# medusa-charger.net
KiCad netlist of a schematic drawn in Altium Designer
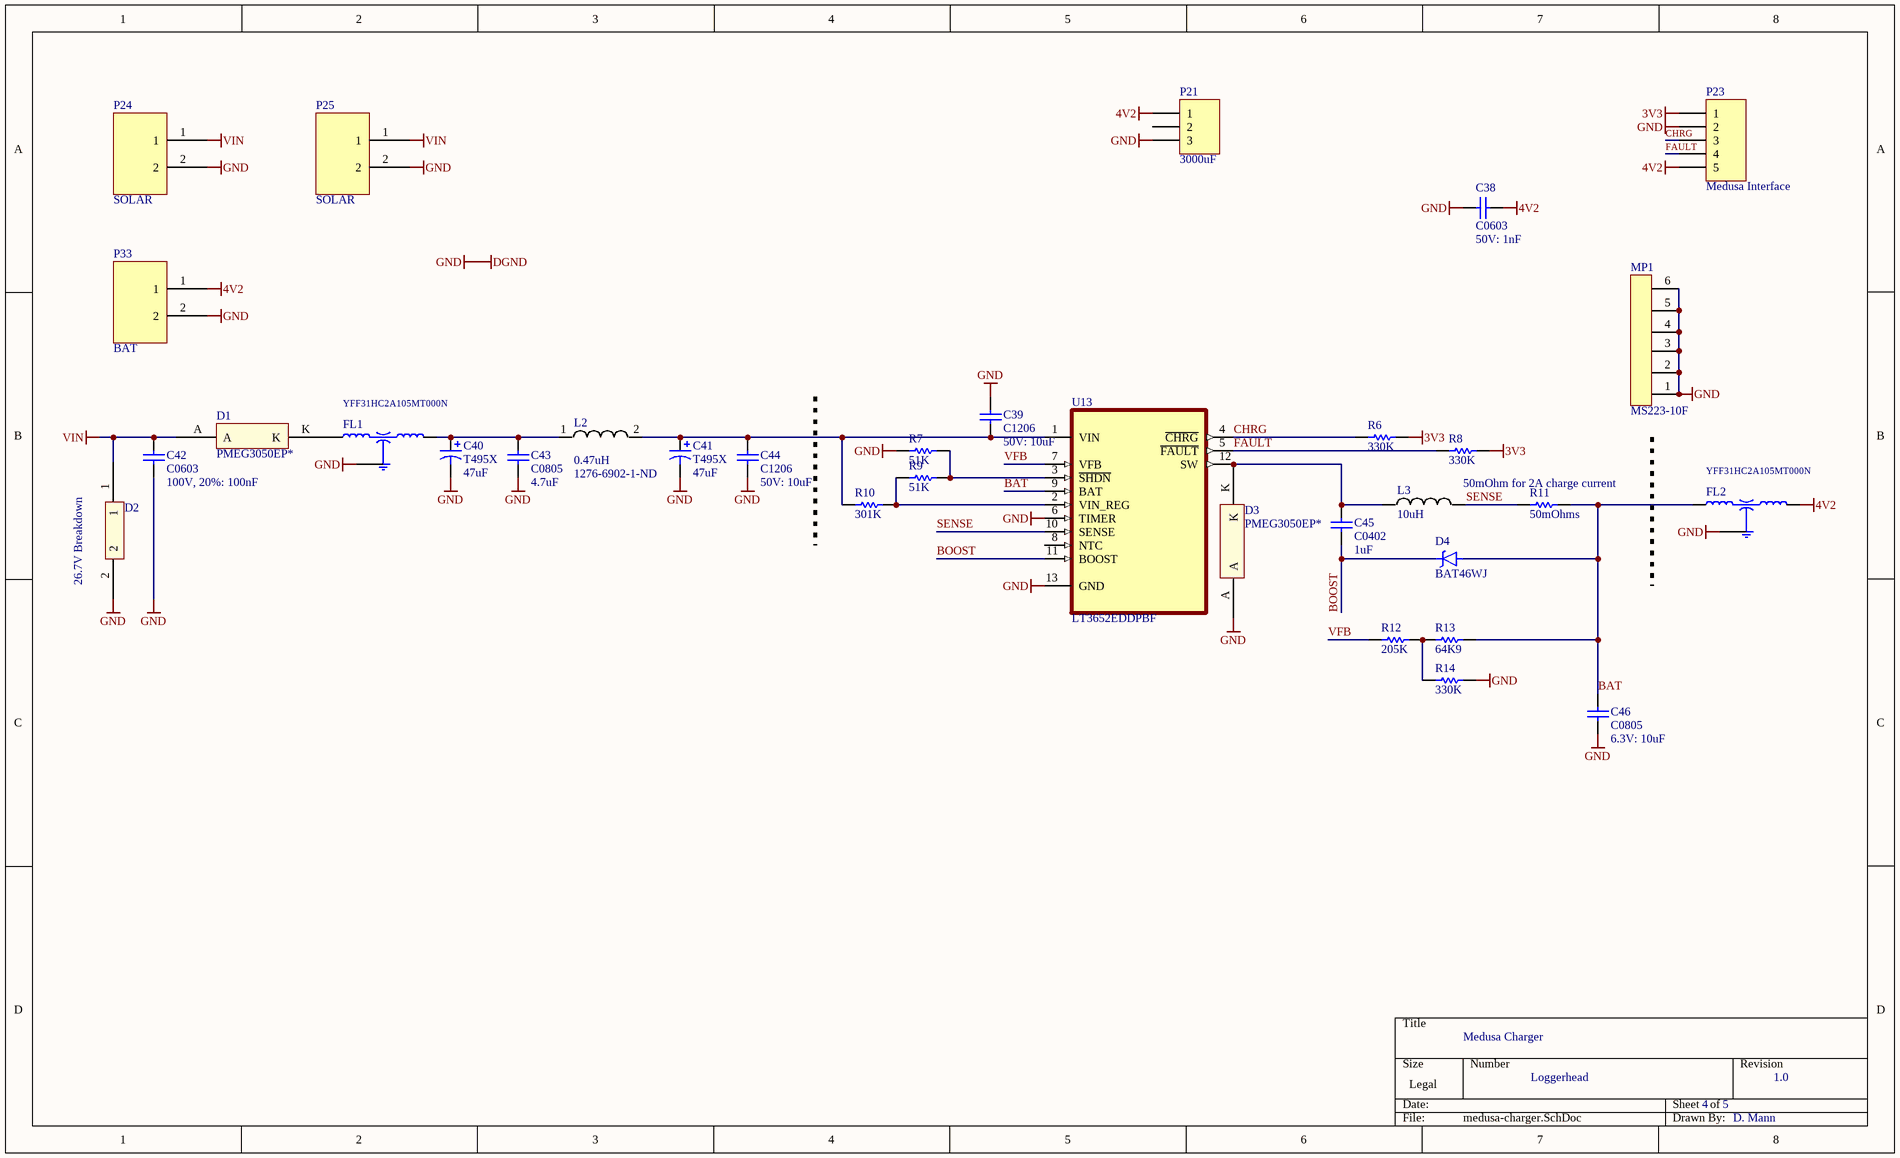
[diagram p0: medusa-charger.SchDoc]

(export (version "E")
  (design (tool "Eeschema 10.0.6"))
  (components
    (comp (ref "C38")
      (value "C0603")
      (footprint "0603")
      (description "Ceramic Chip Capacitor - Standard")
      (fields (field (name "50V") "1nF") (field (name "PUBLISHER") "Altium Limited"))
      (libsource (lib "KEMET Chip Capacitor") (part "C0603"))
    )
    (comp (ref "C39")
      (value "C1206")
      (footprint "1206")
      (description "Ceramic Chip Capacitor - Standard")
      (fields (field (name "50V") "10uF") (field (name "PUBLISHER") "Altium Limited"))
      (libsource (lib "KEMET Chip Capacitor") (part "C1206"))
    )
    (comp (ref "C40")
      (value "T495X")
      (footprint "X")
      (description "Solid Tantalum Chip Capacitor, Standard T495 Series - 35V 10%")
      (fields (field (name "ALTIUM_VALUE") "47uF") (field (name "PUBLISHER") "Altium Limited"))
      (libsource (lib "KEMET Chip Capacitor") (part "T495X"))
    )
    (comp (ref "C41")
      (value "T495X")
      (footprint "X")
      (description "Solid Tantalum Chip Capacitor, Standard T495 Series - 35V 10%")
      (fields (field (name "ALTIUM_VALUE") "47uF") (field (name "PUBLISHER") "Altium Limited"))
      (libsource (lib "KEMET Chip Capacitor") (part "T495X"))
    )
    (comp (ref "C42")
      (value "C0603")
      (footprint "0603")
      (description "100V 20%")
      (fields (field (name "100V, 20%") "100nF") (field (name "PUBLISHER") "Altium Limited"))
      (libsource (lib "KEMET Chip Capacitor") (part "C0603"))
    )
    (comp (ref "C43")
      (value "C0805")
      (footprint "0805")
      (description "Ceramic Chip Capacitor - Standard")
      (fields (field (name "ALTIUM_VALUE") "4.7uF") (field (name "PUBLISHER") "Altium Limited"))
      (libsource (lib "KEMET Chip Capacitor") (part "C0805"))
    )
    (comp (ref "C44")
      (value "C1206")
      (footprint "1206")
      (description "Ceramic Chip Capacitor - Standard")
      (fields (field (name "50V") "10uF") (field (name "PUBLISHER") "Altium Limited"))
      (libsource (lib "KEMET Chip Capacitor") (part "C1206"))
    )
    (comp (ref "C45")
      (value "C0402")
      (footprint "0402")
      (description "Ceramic Chip Capacitor - Standard")
      (fields (field (name "ALTIUM_VALUE") "1uF") (field (name "PUBLISHER") "Altium Limited"))
      (libsource (lib "KEMET Chip Capacitor") (part "C0402"))
    )
    (comp (ref "C46")
      (value "C0805")
      (footprint "0805")
      (description "Ceramic Chip Capacitor - Standard")
      (fields (field (name "6.3V") "10uF") (field (name "PUBLISHER") "Altium Limited"))
      (libsource (lib "KEMET Chip Capacitor") (part "C0805"))
    )
    (comp (ref "D1")
      (value "PMEG3050EP*")
      (footprint "Diode_PMEG3050EP")
      (libsource (lib "") (part "Diode_PMEG3050EP_1"))
    )
    (comp (ref "D2")
      (value "26.7V Breakdown")
      (footprint "SMBJ24CA")
      (libsource (lib "Loggerhead") (part "SMBJ24CA"))
    )
    (comp (ref "D3")
      (value "PMEG3050EP*")
      (footprint "Diode_PMEG3050EP")
      (libsource (lib "Loggerhead") (part "Diode_PMEG3050EP"))
    )
    (comp (ref "D4")
      (value "BAT46WJ")
      (footprint "SOD-323")
      (description "Diode Schottky 100V 250mA (DC) Surface Mount SOD-323F")
      (fields (field (name "MF") "NXP Semiconductors"))
      (libsource (lib "BAT46WJ") (part "BAT46WJ"))
    )
    (comp (ref "FL1")
      (value "YFF31HC2A105MT000N")
      (footprint "FIL_YFF31HC2A105MT000N")
      (description "1ÂµF Feed Through Capacitor 100V 6A 5mOhm 1206 (3216 Metric), 4 PC Pad")
      (fields (field (name "MF") "TDK"))
      (libsource (lib "YFF31HC2A105MT000N") (part "YFF31HC2A105MT000N"))
    )
    (comp (ref "FL2")
      (value "YFF31HC2A105MT000N")
      (footprint "FIL_YFF31HC2A105MT000N")
      (description "1ÂµF Feed Through Capacitor 100V 6A 5mOhm 1206 (3216 Metric), 4 PC Pad")
      (fields (field (name "MF") "TDK"))
      (libsource (lib "YFF31HC2A105MT000N") (part "YFF31HC2A105MT000N"))
    )
    (comp (ref "L2")
      (value "0.47uH")
      (footprint "Inductor2016")
      (fields
        (field (name "SUPPLIER PART NUMBER 1") "1276-6902-1-ND")
        (field (name "Comment") "Inductor2016")
      )
      (libsource (lib "Loggerhead") (part "Inductor2016"))
    )
    (comp (ref "L3")
      (value "10uH")
      (footprint "Inductor0630CDMCD")
      (libsource (lib "Loggerhead") (part "Inductor_0630CDMCD"))
    )
    (comp (ref "MP1")
      (value "MS223-10F")
      (footprint "MS223-10F")
      (description "RF Shield")
      (libsource (lib "Loggerhead") (part "MS223-10F"))
    )
    (comp (ref "P21")
      (value "3000uF")
      (footprint "HDR1X3")
      (description "Header, 3-Pin")
      (fields (field (name "PUBLISHER") "Altium Limited"))
      (libsource (lib "Miscellaneous Connectors") (part "Header 3"))
    )
    (comp (ref "P23")
      (value "Medusa Interface")
      (footprint "HDR1X5")
      (description "Header, 5-Pin")
      (fields (field (name "PUBLISHER") "Altium Limited"))
      (libsource (lib "Miscellaneous Connectors") (part "Header 5"))
    )
    (comp (ref "P24")
      (value "SOLAR")
      (footprint "HDR_2x1_2mm")
      (libsource (lib "Loggerhead") (part "HDR_2x1_2mm"))
    )
    (comp (ref "P25")
      (value "SOLAR")
      (footprint "HDR_2x1_2mm")
      (libsource (lib "Loggerhead") (part "HDR_2x1_2mm"))
    )
    (comp (ref "P33")
      (value "BAT")
      (footprint "HDR_2x1_2mm")
      (libsource (lib "Loggerhead") (part "HDR_2x1_2mm"))
    )
    (comp (ref "R6")
      (value "330K")
      (footprint "3-0603")
      (fields (field (name "PUBLISHER") "Altium Limited"))
      (libsource (lib "Panasonic Resistor") (part "ERJ3EK"))
    )
    (comp (ref "R7")
      (value "51K")
      (footprint "3-0603")
      (fields (field (name "PUBLISHER") "Altium Limited"))
      (libsource (lib "Panasonic Resistor") (part "ERJ3EK"))
    )
    (comp (ref "R8")
      (value "330K")
      (footprint "3-0603")
      (fields (field (name "PUBLISHER") "Altium Limited"))
      (libsource (lib "Panasonic Resistor") (part "ERJ3EK"))
    )
    (comp (ref "R9")
      (value "51K")
      (footprint "3-0603")
      (fields (field (name "PUBLISHER") "Altium Limited"))
      (libsource (lib "Panasonic Resistor") (part "ERJ3EK"))
    )
    (comp (ref "R10")
      (value "301K")
      (footprint "3-0603")
      (fields (field (name "PUBLISHER") "Altium Limited"))
      (libsource (lib "Panasonic Resistor") (part "ERJ3EK"))
    )
    (comp (ref "R11")
      (value "50mOhms")
      (footprint "8-1206")
      (description "Precision Thick Film Chip Resistor, 10 Ohm to 2.2M Ohm Range, 1% Tolerance, 1206 Size, 0.125 W")
      (fields (field (name "PUBLISHER") "Altium Limited"))
      (libsource (lib "Panasonic Resistor") (part "ERJ8EN"))
    )
    (comp (ref "R12")
      (value "205K")
      (footprint "3-0603")
      (fields (field (name "PUBLISHER") "Altium Limited"))
      (libsource (lib "Panasonic Resistor") (part "ERJ3EK"))
    )
    (comp (ref "R13")
      (value "64K9")
      (footprint "3-0603")
      (fields (field (name "PUBLISHER") "Altium Limited"))
      (libsource (lib "Panasonic Resistor") (part "ERJ3EK"))
    )
    (comp (ref "R14")
      (value "330K")
      (footprint "3-0603")
      (fields (field (name "PUBLISHER") "Altium Limited"))
      (libsource (lib "Panasonic Resistor") (part "ERJ3EK"))
    )
    (comp (ref "U13")
      (value "LT3652EDDPBF")
      (footprint "DFN300X300X80-13N")
      (description "Power Tracking 2A Battery Charger for Solar Power")
      (libsource (lib "LT3652EDDPBF") (part "LT3652EDDPBF"))
    )
  )
  (nets
    (net (code "1") (name "/BAT") (class "Default")
      (node (ref "C46") (pin "2") (pinfunction "2_2") (pintype "passive"))
      (node (ref "D4") (pin "A") (pinfunction "A_A") (pintype "passive"))
      (node (ref "FL2") (pin "1") (pinfunction "IN/OUT_1") (pintype "passive"))
      (node (ref "R11") (pin "2") (pinfunction "2_2") (pintype "passive"))
      (node (ref "R13") (pin "1") (pinfunction "1_1") (pintype "passive"))
      (node (ref "U13") (pin "9") (pinfunction "BAT_9") (pintype "input"))
    )
    (net (code "2") (name "/BOOST") (class "Default")
      (node (ref "C45") (pin "1") (pinfunction "1_1") (pintype "passive"))
      (node (ref "D4") (pin "C") (pinfunction "C_C") (pintype "passive"))
      (node (ref "U13") (pin "11") (pinfunction "BOOST_11") (pintype "input"))
    )
    (net (code "3") (name "/CHRG") (class "Default")
      (node (ref "P23") (pin "3") (pinfunction "3_3") (pintype "passive"))
      (node (ref "R6") (pin "2") (pinfunction "2_2") (pintype "passive"))
      (node (ref "U13") (pin "4") (pinfunction "~{CHRG}_4") (pintype "output"))
    )
    (net (code "4") (name "/FAULT") (class "Default")
      (node (ref "P23") (pin "4") (pinfunction "4_4") (pintype "passive"))
      (node (ref "R8") (pin "2") (pinfunction "2_2") (pintype "passive"))
      (node (ref "U13") (pin "5") (pinfunction "~{FAULT}_5") (pintype "output"))
    )
    (net (code "5") (name "/SENSE") (class "Default")
      (node (ref "L3") (pin "2") (pinfunction "2_2") (pintype "passive"))
      (node (ref "R11") (pin "1") (pinfunction "1_1") (pintype "passive"))
      (node (ref "U13") (pin "10") (pinfunction "SENSE_10") (pintype "input"))
    )
    (net (code "6") (name "/VFB") (class "Default")
      (node (ref "R12") (pin "2") (pinfunction "2_2") (pintype "passive"))
      (node (ref "U13") (pin "7") (pinfunction "VFB_7") (pintype "input"))
    )
    (net (code "7") (name "3V3") (class "Default")
      (node (ref "P23") (pin "1") (pinfunction "1_1") (pintype "passive"))
      (node (ref "R6") (pin "1") (pinfunction "1_1") (pintype "passive"))
      (node (ref "R8") (pin "1") (pinfunction "1_1") (pintype "passive"))
    )
    (net (code "8") (name "4V2") (class "Default")
      (node (ref "C38") (pin "2") (pinfunction "2_2") (pintype "passive"))
      (node (ref "FL2") (pin "3") (pinfunction "OUT/IN_3") (pintype "passive"))
      (node (ref "P21") (pin "1") (pinfunction "1_1") (pintype "passive"))
      (node (ref "P23") (pin "5") (pinfunction "5_5") (pintype "passive"))
      (node (ref "P33") (pin "1") (pinfunction "1_1") (pintype "passive"))
    )
    (net (code "9") (name "DGND") (class "Default")
      (node (ref "C38") (pin "1") (pinfunction "1_1") (pintype "passive"))
      (node (ref "C39") (pin "1") (pinfunction "1_1") (pintype "passive"))
      (node (ref "C40") (pin "2") (pinfunction "2_2") (pintype "passive"))
      (node (ref "C41") (pin "2") (pinfunction "2_2") (pintype "passive"))
      (node (ref "C42") (pin "1") (pinfunction "1_1") (pintype "passive"))
      (node (ref "C43") (pin "1") (pinfunction "1_1") (pintype "passive"))
      (node (ref "C44") (pin "1") (pinfunction "1_1") (pintype "passive"))
      (node (ref "C46") (pin "1") (pinfunction "1_1") (pintype "passive"))
      (node (ref "D2") (pin "2") (pinfunction "2_2") (pintype "passive"))
      (node (ref "D3") (pin "A") (pinfunction "A_A") (pintype "passive"))
      (node (ref "FL1") (pin "2_4") (pinfunction "GND_2_4") (pintype "power_in"))
      (node (ref "FL2") (pin "2_4") (pinfunction "GND_2_4") (pintype "power_in"))
      (node (ref "MP1") (pin "1") (pinfunction "1_1") (pintype "passive"))
      (node (ref "MP1") (pin "2") (pinfunction "2_2") (pintype "passive"))
      (node (ref "MP1") (pin "3") (pinfunction "3_3") (pintype "passive"))
      (node (ref "MP1") (pin "4") (pinfunction "4_4") (pintype "passive"))
      (node (ref "MP1") (pin "5") (pinfunction "5_5") (pintype "passive"))
      (node (ref "MP1") (pin "6") (pinfunction "6_6") (pintype "passive"))
      (node (ref "P21") (pin "3") (pinfunction "3_3") (pintype "passive"))
      (node (ref "P23") (pin "2") (pinfunction "2_2") (pintype "passive"))
      (node (ref "P24") (pin "2") (pinfunction "2_2") (pintype "passive"))
      (node (ref "P25") (pin "2") (pinfunction "2_2") (pintype "passive"))
      (node (ref "P33") (pin "2") (pinfunction "2_2") (pintype "passive"))
      (node (ref "R14") (pin "1") (pinfunction "1_1") (pintype "passive"))
      (node (ref "R7") (pin "1") (pinfunction "1_1") (pintype "passive"))
      (node (ref "U13") (pin "13") (pinfunction "GND_13") (pintype "passive"))
      (node (ref "U13") (pin "6") (pinfunction "TIMER_6") (pintype "input"))
    )
    (net (code "10") (name "Net-(FL1-IN{slash}OUT)") (class "Default")
      (node (ref "D1") (pin "K") (pinfunction "K_K") (pintype "passive"))
      (node (ref "FL1") (pin "1") (pinfunction "IN/OUT_1") (pintype "passive"))
    )
    (net (code "11") (name "Net-(FL1-OUT{slash}IN)") (class "Default")
      (node (ref "C40") (pin "1") (pinfunction "1_1") (pintype "passive"))
      (node (ref "C43") (pin "2") (pinfunction "2_2") (pintype "passive"))
      (node (ref "FL1") (pin "3") (pinfunction "OUT/IN_3") (pintype "passive"))
      (node (ref "L2") (pin "1") (pinfunction "1_1") (pintype "passive"))
    )
    (net (code "12") (name "Net-(R12-Pad1)") (class "Default")
      (node (ref "R12") (pin "1") (pinfunction "1_1") (pintype "passive"))
      (node (ref "R13") (pin "2") (pinfunction "2_2") (pintype "passive"))
      (node (ref "R14") (pin "2") (pinfunction "2_2") (pintype "passive"))
    )
    (net (code "13") (name "Net-(U13-SW)") (class "Default")
      (node (ref "C45") (pin "2") (pinfunction "2_2") (pintype "passive"))
      (node (ref "D3") (pin "K") (pinfunction "K_K") (pintype "passive"))
      (node (ref "L3") (pin "1") (pinfunction "1_1") (pintype "passive"))
      (node (ref "U13") (pin "12") (pinfunction "SW_12") (pintype "output"))
    )
    (net (code "14") (name "Net-(U13-VIN)") (class "Default")
      (node (ref "C39") (pin "2") (pinfunction "2_2") (pintype "passive"))
      (node (ref "C41") (pin "1") (pinfunction "1_1") (pintype "passive"))
      (node (ref "C44") (pin "2") (pinfunction "2_2") (pintype "passive"))
      (node (ref "L2") (pin "2") (pinfunction "2_2") (pintype "passive"))
      (node (ref "R10") (pin "1") (pinfunction "1_1") (pintype "passive"))
      (node (ref "U13") (pin "1") (pinfunction "VIN_1") (pintype "power_in"))
    )
    (net (code "15") (name "Net-(U13-VIN_REG)") (class "Default")
      (node (ref "R10") (pin "2") (pinfunction "2_2") (pintype "passive"))
      (node (ref "R9") (pin "1") (pinfunction "1_1") (pintype "passive"))
      (node (ref "U13") (pin "2") (pinfunction "VIN_REG_2") (pintype "input"))
    )
    (net (code "16") (name "Net-(U13-~{SHDN})") (class "Default")
      (node (ref "R7") (pin "2") (pinfunction "2_2") (pintype "passive"))
      (node (ref "R9") (pin "2") (pinfunction "2_2") (pintype "passive"))
      (node (ref "U13") (pin "3") (pinfunction "~{SHDN}_3") (pintype "input"))
    )
    (net (code "17") (name "VIN") (class "Default")
      (node (ref "C42") (pin "2") (pinfunction "2_2") (pintype "passive"))
      (node (ref "D1") (pin "A") (pinfunction "A_A") (pintype "passive"))
      (node (ref "D2") (pin "1") (pinfunction "1_1") (pintype "passive"))
      (node (ref "P24") (pin "1") (pinfunction "1_1") (pintype "passive"))
      (node (ref "P25") (pin "1") (pinfunction "1_1") (pintype "passive"))
    )
    (net (code "18") (name "unconnected-(P21-Pad2)") (class "Default")
      (node (ref "P21") (pin "2") (pinfunction "2_2") (pintype "passive"))
    )
    (net (code "19") (name "unconnected-(U13-NTC-Pad8)") (class "Default")
      (node (ref "U13") (pin "8") (pinfunction "NTC_8") (pintype "input"))
    )
  )
)
